# Schematic.net
KiCad netlist of a schematic drawn in Altium Designer
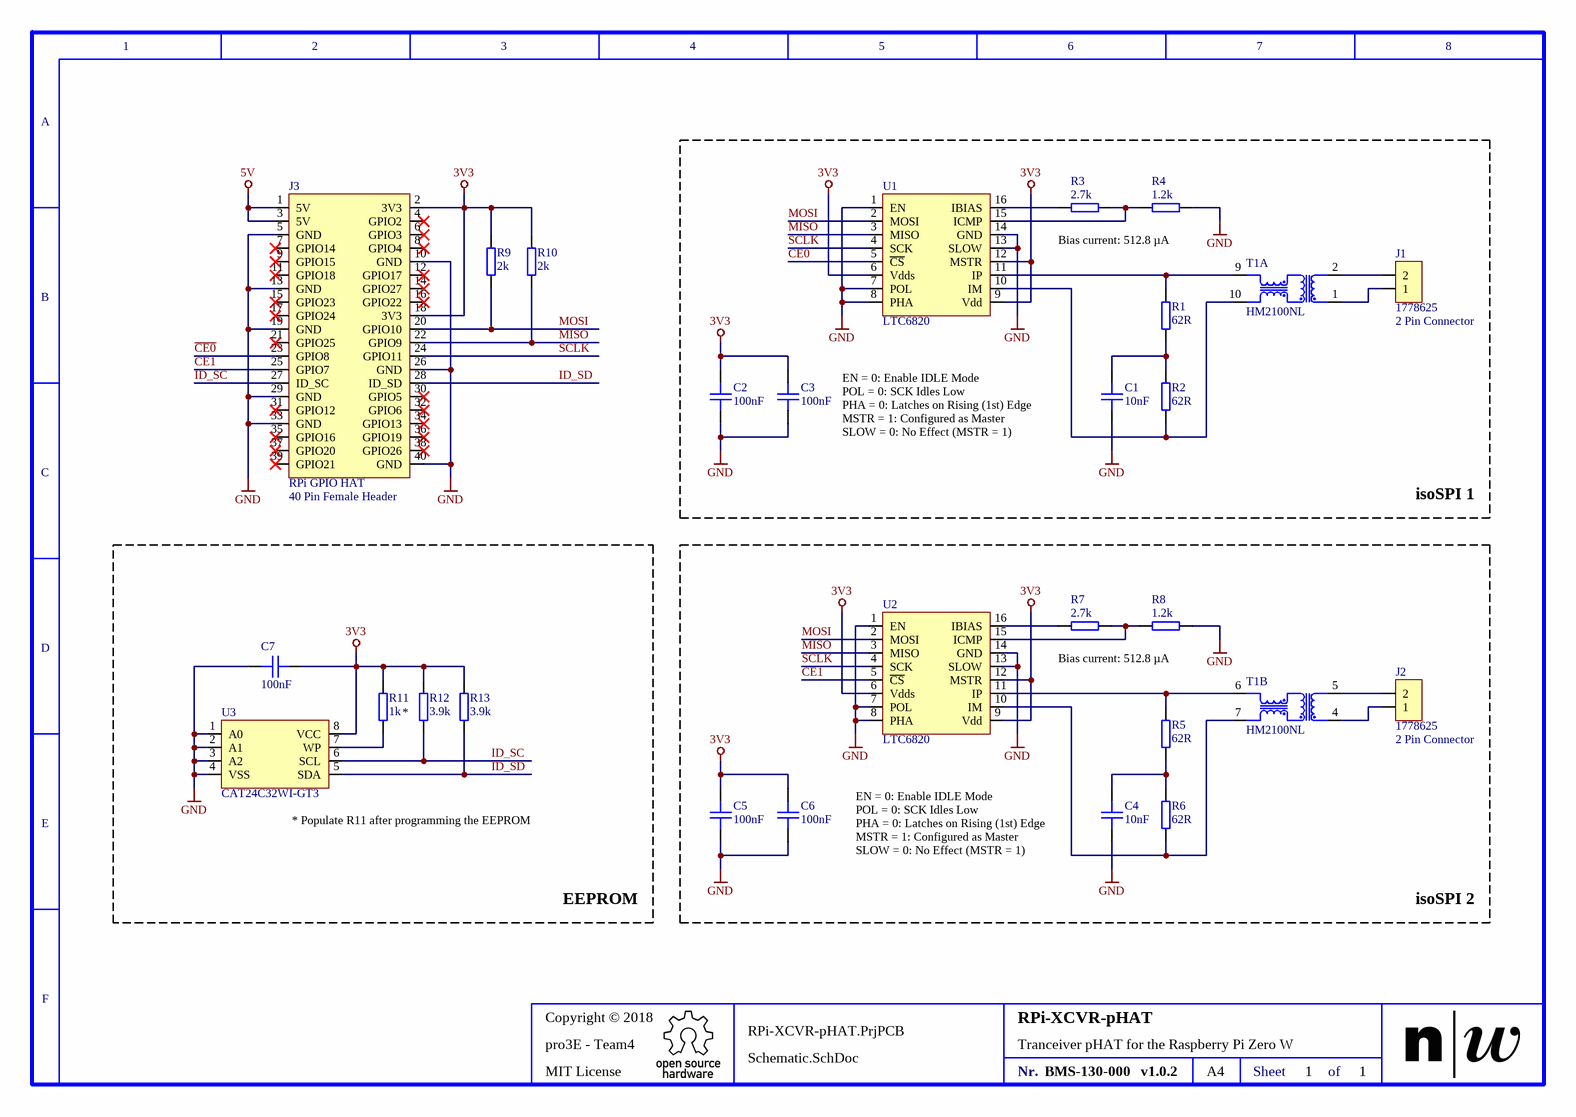
[diagram p0: Schematic.SchDoc]

(export (version "E")
  (design (tool "Eeschema 10.0.6"))
  (components
    (comp (ref "C1") (value "10nF") (footprint "CAP 0603") (libsource (lib "SVNDatabase") (part "Capacitor")))
    (comp (ref "C2")
      (value "100nF")
      (footprint "CAP 0603")
      (libsource (lib "SVNDatabase") (part "Capacitor"))
    )
    (comp (ref "C3")
      (value "100nF")
      (footprint "CAP 0603")
      (libsource (lib "SVNDatabase") (part "Capacitor"))
    )
    (comp (ref "C4") (value "10nF") (footprint "CAP 0603") (libsource (lib "SVNDatabase") (part "Capacitor")))
    (comp (ref "C5")
      (value "100nF")
      (footprint "CAP 0603")
      (libsource (lib "SVNDatabase") (part "Capacitor"))
    )
    (comp (ref "C6")
      (value "100nF")
      (footprint "CAP 0603")
      (libsource (lib "SVNDatabase") (part "Capacitor"))
    )
    (comp (ref "C7")
      (value "100nF")
      (footprint "CAP 0603")
      (libsource (lib "SVNDatabase") (part "Capacitor"))
    )
    (comp (ref "J1")
      (value "1778625")
      (footprint "PTSM 0.5 2 HH THT")
      (description "2 Pin Connector")
      (fields (field (name "DESC") "2 Pin Connector"))
      (libsource (lib "SVNDatabase") (part "2 Pin"))
    )
    (comp (ref "J2")
      (value "1778625")
      (footprint "PTSM 0.5 2 HH THT")
      (description "2 Pin Connector")
      (fields (field (name "DESC") "2 Pin Connector"))
      (libsource (lib "SVNDatabase") (part "2 Pin"))
    )
    (comp (ref "J3")
      (value "RPi GPIO HAT")
      (footprint "Pin Header 2x20 THT 2.54 Female")
      (description "40 Pin Female Header")
      (fields (field (name "DESCR") "40 Pin Female Header"))
      (libsource (lib "SVNDatabase") (part "40 Pin RPi HAT"))
    )
    (comp (ref "R1")
      (value "62R")
      (footprint "0603")
      (fields (field (name "TOLERANCE") "1%"))
      (libsource (lib "SVNDatabase") (part "R"))
    )
    (comp (ref "R2")
      (value "62R")
      (footprint "0603")
      (fields (field (name "TOLERANCE") "1%"))
      (libsource (lib "SVNDatabase") (part "R"))
    )
    (comp (ref "R3")
      (value "2.7k")
      (footprint "0603")
      (fields (field (name "TOLERANCE") "1%"))
      (libsource (lib "SVNDatabase") (part "R"))
    )
    (comp (ref "R4")
      (value "1.2k")
      (footprint "0603")
      (fields (field (name "TOLERANCE") "1%"))
      (libsource (lib "SVNDatabase") (part "R"))
    )
    (comp (ref "R5")
      (value "62R")
      (footprint "0603")
      (fields (field (name "TOLERANCE") "1%"))
      (libsource (lib "SVNDatabase") (part "R"))
    )
    (comp (ref "R6")
      (value "62R")
      (footprint "0603")
      (fields (field (name "TOLERANCE") "1%"))
      (libsource (lib "SVNDatabase") (part "R"))
    )
    (comp (ref "R7")
      (value "2.7k")
      (footprint "0603")
      (fields (field (name "TOLERANCE") "1%"))
      (libsource (lib "SVNDatabase") (part "R"))
    )
    (comp (ref "R8")
      (value "1.2k")
      (footprint "0603")
      (fields (field (name "TOLERANCE") "1%"))
      (libsource (lib "SVNDatabase") (part "R"))
    )
    (comp (ref "R9")
      (value "2k")
      (footprint "0603")
      (fields (field (name "TOLERANCE") "1%"))
      (libsource (lib "SVNDatabase") (part "R"))
    )
    (comp (ref "R10")
      (value "2k")
      (footprint "0603")
      (fields (field (name "TOLERANCE") "1%"))
      (libsource (lib "SVNDatabase") (part "R"))
    )
    (comp (ref "R11")
      (value "1k")
      (footprint "0603")
      (fields (field (name "TOLERANCE") "1%"))
      (libsource (lib "SVNDatabase") (part "R"))
    )
    (comp (ref "R12")
      (value "3.9k")
      (footprint "0603")
      (fields (field (name "TOLERANCE") "1%"))
      (libsource (lib "SVNDatabase") (part "R"))
    )
    (comp (ref "R13")
      (value "3.9k")
      (footprint "0603")
      (fields (field (name "TOLERANCE") "1%"))
      (libsource (lib "SVNDatabase") (part "R"))
    )
    (comp (ref "T1")
      (value "HM2100NL")
      (footprint "HM2100NL")
      (description "BMS Communication Transformer with Choke")
      (fields (field (name "TOLERANCE") "50%"))
      (libsource (lib "") (part "HM2100NL_1"))
    )
    (comp (ref "U1")
      (value "LTC6820")
      (footprint "MSOP-16")
      (description "Isolated SPI Communications Interface")
      (libsource (lib "SVNDatabase") (part "LTC6820"))
    )
    (comp (ref "U2")
      (value "LTC6820")
      (footprint "MSOP-16")
      (description "Isolated SPI Communications Interface")
      (libsource (lib "SVNDatabase") (part "LTC6820"))
    )
    (comp (ref "U3")
      (value "CAT24C32WI-GT3")
      (footprint "SO-8")
      (description "EEPROM Memory IC 32Kb")
      (libsource (lib "SVNDatabase") (part "CAT24C32"))
    )
  )
  (nets
    (net (code "1") (name "/ID_SC") (class "Default")
      (node (ref "J3") (pin "27") (pinfunction "ID_SC_27") (pintype "passive"))
      (node (ref "R12") (pin "1") (pinfunction "1_1") (pintype "passive"))
      (node (ref "U3") (pin "6") (pinfunction "SCL_6") (pintype "passive"))
    )
    (net (code "2") (name "/ID_SD") (class "Default")
      (node (ref "J3") (pin "28") (pinfunction "ID_SD_28") (pintype "passive"))
      (node (ref "R13") (pin "1") (pinfunction "1_1") (pintype "passive"))
      (node (ref "U3") (pin "5") (pinfunction "SDA_5") (pintype "passive"))
    )
    (net (code "3") (name "/MISO") (class "Default")
      (node (ref "J3") (pin "22") (pinfunction "GPIO9_22") (pintype "passive"))
      (node (ref "R10") (pin "1") (pinfunction "1_1") (pintype "passive"))
      (node (ref "U1") (pin "3") (pinfunction "MISO_3") (pintype "passive"))
      (node (ref "U2") (pin "3") (pinfunction "MISO_3") (pintype "passive"))
    )
    (net (code "4") (name "/MOSI") (class "Default")
      (node (ref "J3") (pin "20") (pinfunction "GPIO10_20") (pintype "passive"))
      (node (ref "R9") (pin "1") (pinfunction "1_1") (pintype "passive"))
      (node (ref "U1") (pin "2") (pinfunction "MOSI_2") (pintype "passive"))
      (node (ref "U2") (pin "2") (pinfunction "MOSI_2") (pintype "passive"))
    )
    (net (code "5") (name "/SCLK") (class "Default")
      (node (ref "J3") (pin "24") (pinfunction "GPIO11_24") (pintype "passive"))
      (node (ref "U1") (pin "4") (pinfunction "SCK_4") (pintype "passive"))
      (node (ref "U2") (pin "4") (pinfunction "SCK_4") (pintype "passive"))
    )
    (net (code "6") (name "/~{CE0}") (class "Default")
      (node (ref "J3") (pin "23") (pinfunction "GPIO8_23") (pintype "passive"))
      (node (ref "U1") (pin "5") (pinfunction "~{CS}_5") (pintype "passive"))
    )
    (net (code "7") (name "/~{CE1}") (class "Default")
      (node (ref "J3") (pin "25") (pinfunction "GPIO7_25") (pintype "passive"))
      (node (ref "U2") (pin "5") (pinfunction "~{CS}_5") (pintype "passive"))
    )
    (net (code "8") (name "3V3") (class "Default")
      (node (ref "C2") (pin "2") (pinfunction "2_2") (pintype "passive"))
      (node (ref "C3") (pin "2") (pinfunction "2_2") (pintype "passive"))
      (node (ref "C5") (pin "2") (pinfunction "2_2") (pintype "passive"))
      (node (ref "C6") (pin "2") (pinfunction "2_2") (pintype "passive"))
      (node (ref "C7") (pin "1") (pinfunction "1_1") (pintype "passive"))
      (node (ref "J3") (pin "18") (pinfunction "3V3_18") (pintype "passive"))
      (node (ref "J3") (pin "2") (pinfunction "3V3_2") (pintype "passive"))
      (node (ref "R10") (pin "2") (pinfunction "2_2") (pintype "passive"))
      (node (ref "R11") (pin "2") (pinfunction "2_2") (pintype "passive"))
      (node (ref "R12") (pin "2") (pinfunction "2_2") (pintype "passive"))
      (node (ref "R13") (pin "2") (pinfunction "2_2") (pintype "passive"))
      (node (ref "R9") (pin "2") (pinfunction "2_2") (pintype "passive"))
      (node (ref "U1") (pin "12") (pinfunction "MSTR_12") (pintype "passive"))
      (node (ref "U1") (pin "6") (pinfunction "Vdds_6") (pintype "passive"))
      (node (ref "U1") (pin "9") (pinfunction "Vdd_9") (pintype "passive"))
      (node (ref "U2") (pin "12") (pinfunction "MSTR_12") (pintype "passive"))
      (node (ref "U2") (pin "6") (pinfunction "Vdds_6") (pintype "passive"))
      (node (ref "U2") (pin "9") (pinfunction "Vdd_9") (pintype "passive"))
      (node (ref "U3") (pin "8") (pinfunction "VCC_8") (pintype "passive"))
    )
    (net (code "9") (name "5V") (class "Default")
      (node (ref "J3") (pin "1") (pinfunction "5V_1") (pintype "passive"))
      (node (ref "J3") (pin "3") (pinfunction "5V_3") (pintype "passive"))
    )
    (net (code "10") (name "GND") (class "Default")
      (node (ref "C1") (pin "1") (pinfunction "1_1") (pintype "passive"))
      (node (ref "C2") (pin "1") (pinfunction "1_1") (pintype "passive"))
      (node (ref "C3") (pin "1") (pinfunction "1_1") (pintype "passive"))
      (node (ref "C4") (pin "1") (pinfunction "1_1") (pintype "passive"))
      (node (ref "C5") (pin "1") (pinfunction "1_1") (pintype "passive"))
      (node (ref "C6") (pin "1") (pinfunction "1_1") (pintype "passive"))
      (node (ref "C7") (pin "2") (pinfunction "2_2") (pintype "passive"))
      (node (ref "J3") (pin "10") (pinfunction "GND_10") (pintype "passive"))
      (node (ref "J3") (pin "13") (pinfunction "GND_13") (pintype "passive"))
      (node (ref "J3") (pin "19") (pinfunction "GND_19") (pintype "passive"))
      (node (ref "J3") (pin "26") (pinfunction "GND_26") (pintype "passive"))
      (node (ref "J3") (pin "29") (pinfunction "GND_29") (pintype "passive"))
      (node (ref "J3") (pin "33") (pinfunction "GND_33") (pintype "passive"))
      (node (ref "J3") (pin "40") (pinfunction "GND_40") (pintype "passive"))
      (node (ref "J3") (pin "5") (pinfunction "GND_5") (pintype "passive"))
      (node (ref "R4") (pin "2") (pinfunction "2_2") (pintype "passive"))
      (node (ref "R8") (pin "2") (pinfunction "2_2") (pintype "passive"))
      (node (ref "U1") (pin "1") (pinfunction "EN_1") (pintype "passive"))
      (node (ref "U1") (pin "13") (pinfunction "SLOW_13") (pintype "passive"))
      (node (ref "U1") (pin "14") (pinfunction "GND_14") (pintype "passive"))
      (node (ref "U1") (pin "7") (pinfunction "POL_7") (pintype "passive"))
      (node (ref "U1") (pin "8") (pinfunction "PHA_8") (pintype "passive"))
      (node (ref "U2") (pin "1") (pinfunction "EN_1") (pintype "passive"))
      (node (ref "U2") (pin "13") (pinfunction "SLOW_13") (pintype "passive"))
      (node (ref "U2") (pin "14") (pinfunction "GND_14") (pintype "passive"))
      (node (ref "U2") (pin "7") (pinfunction "POL_7") (pintype "passive"))
      (node (ref "U2") (pin "8") (pinfunction "PHA_8") (pintype "passive"))
      (node (ref "U3") (pin "1") (pinfunction "A0_1") (pintype "passive"))
      (node (ref "U3") (pin "2") (pinfunction "A1_2") (pintype "passive"))
      (node (ref "U3") (pin "3") (pinfunction "A2_3") (pintype "passive"))
      (node (ref "U3") (pin "4") (pinfunction "VSS_4") (pintype "passive"))
    )
    (net (code "11") (name "Net-(C1-Pad2)") (class "Default")
      (node (ref "C1") (pin "2") (pinfunction "2_2") (pintype "passive"))
      (node (ref "R1") (pin "1") (pinfunction "1_1") (pintype "passive"))
      (node (ref "R2") (pin "2") (pinfunction "2_2") (pintype "passive"))
    )
    (net (code "12") (name "Net-(C4-Pad2)") (class "Default")
      (node (ref "C4") (pin "2") (pinfunction "2_2") (pintype "passive"))
      (node (ref "R5") (pin "1") (pinfunction "1_1") (pintype "passive"))
      (node (ref "R6") (pin "2") (pinfunction "2_2") (pintype "passive"))
    )
    (net (code "13") (name "Net-(J1-Pad1)") (class "Default")
      (node (ref "J1") (pin "1") (pinfunction "1_1") (pintype "passive"))
      (node (ref "T1") (pin "1") (pinfunction "1_1") (pintype "passive"))
    )
    (net (code "14") (name "Net-(J1-Pad2)") (class "Default")
      (node (ref "J1") (pin "2") (pinfunction "2_2") (pintype "passive"))
      (node (ref "T1") (pin "2") (pinfunction "2_2") (pintype "passive"))
    )
    (net (code "15") (name "Net-(J2-Pad1)") (class "Default")
      (node (ref "J2") (pin "1") (pinfunction "1_1") (pintype "passive"))
      (node (ref "T1") (pin "4") (pinfunction "4_4") (pintype "passive"))
    )
    (net (code "16") (name "Net-(J2-Pad2)") (class "Default")
      (node (ref "J2") (pin "2") (pinfunction "2_2") (pintype "passive"))
      (node (ref "T1") (pin "5") (pinfunction "5_5") (pintype "passive"))
    )
    (net (code "17") (name "Net-(U1-IBIAS)") (class "Default")
      (node (ref "R3") (pin "1") (pinfunction "1_1") (pintype "passive"))
      (node (ref "U1") (pin "16") (pinfunction "IBIAS_16") (pintype "passive"))
    )
    (net (code "18") (name "Net-(U1-ICMP)") (class "Default")
      (node (ref "R3") (pin "2") (pinfunction "2_2") (pintype "passive"))
      (node (ref "R4") (pin "1") (pinfunction "1_1") (pintype "passive"))
      (node (ref "U1") (pin "15") (pinfunction "ICMP_15") (pintype "passive"))
    )
    (net (code "19") (name "Net-(U1-IM)") (class "Default")
      (node (ref "R2") (pin "1") (pinfunction "1_1") (pintype "passive"))
      (node (ref "T1") (pin "10") (pinfunction "10_10") (pintype "passive"))
      (node (ref "U1") (pin "10") (pinfunction "IM_10") (pintype "passive"))
    )
    (net (code "20") (name "Net-(U1-IP)") (class "Default")
      (node (ref "R1") (pin "2") (pinfunction "2_2") (pintype "passive"))
      (node (ref "T1") (pin "9") (pinfunction "9_9") (pintype "passive"))
      (node (ref "U1") (pin "11") (pinfunction "IP_11") (pintype "passive"))
    )
    (net (code "21") (name "Net-(U2-IBIAS)") (class "Default")
      (node (ref "R7") (pin "1") (pinfunction "1_1") (pintype "passive"))
      (node (ref "U2") (pin "16") (pinfunction "IBIAS_16") (pintype "passive"))
    )
    (net (code "22") (name "Net-(U2-ICMP)") (class "Default")
      (node (ref "R7") (pin "2") (pinfunction "2_2") (pintype "passive"))
      (node (ref "R8") (pin "1") (pinfunction "1_1") (pintype "passive"))
      (node (ref "U2") (pin "15") (pinfunction "ICMP_15") (pintype "passive"))
    )
    (net (code "23") (name "Net-(U2-IM)") (class "Default")
      (node (ref "R6") (pin "1") (pinfunction "1_1") (pintype "passive"))
      (node (ref "T1") (pin "7") (pinfunction "7_7") (pintype "passive"))
      (node (ref "U2") (pin "10") (pinfunction "IM_10") (pintype "passive"))
    )
    (net (code "24") (name "Net-(U2-IP)") (class "Default")
      (node (ref "R5") (pin "2") (pinfunction "2_2") (pintype "passive"))
      (node (ref "T1") (pin "6") (pinfunction "6_6") (pintype "passive"))
      (node (ref "U2") (pin "11") (pinfunction "IP_11") (pintype "passive"))
    )
    (net (code "25") (name "Net-(U3-WP)") (class "Default")
      (node (ref "R11") (pin "1") (pinfunction "1_1") (pintype "passive"))
      (node (ref "U3") (pin "7") (pinfunction "WP_7") (pintype "passive"))
    )
    (net (code "26") (name "unconnected-(J3-GPIO2-Pad4)") (class "Default")
      (node (ref "J3") (pin "4") (pinfunction "GPIO2_4") (pintype "passive+no_connect"))
    )
    (net (code "27") (name "unconnected-(J3-GPIO3-Pad6)") (class "Default")
      (node (ref "J3") (pin "6") (pinfunction "GPIO3_6") (pintype "passive+no_connect"))
    )
    (net (code "28") (name "unconnected-(J3-GPIO4-Pad8)") (class "Default")
      (node (ref "J3") (pin "8") (pinfunction "GPIO4_8") (pintype "passive+no_connect"))
    )
    (net (code "29") (name "unconnected-(J3-GPIO5-Pad30)") (class "Default")
      (node (ref "J3") (pin "30") (pinfunction "GPIO5_30") (pintype "passive+no_connect"))
    )
    (net (code "30") (name "unconnected-(J3-GPIO6-Pad32)") (class "Default")
      (node (ref "J3") (pin "32") (pinfunction "GPIO6_32") (pintype "passive+no_connect"))
    )
    (net (code "31") (name "unconnected-(J3-GPIO12-Pad31)") (class "Default")
      (node (ref "J3") (pin "31") (pinfunction "GPIO12_31") (pintype "passive+no_connect"))
    )
    (net (code "32") (name "unconnected-(J3-GPIO13-Pad34)") (class "Default")
      (node (ref "J3") (pin "34") (pinfunction "GPIO13_34") (pintype "passive+no_connect"))
    )
    (net (code "33") (name "unconnected-(J3-GPIO14-Pad7)") (class "Default")
      (node (ref "J3") (pin "7") (pinfunction "GPIO14_7") (pintype "passive+no_connect"))
    )
    (net (code "34") (name "unconnected-(J3-GPIO15-Pad9)") (class "Default")
      (node (ref "J3") (pin "9") (pinfunction "GPIO15_9") (pintype "passive+no_connect"))
    )
    (net (code "35") (name "unconnected-(J3-GPIO16-Pad35)") (class "Default")
      (node (ref "J3") (pin "35") (pinfunction "GPIO16_35") (pintype "passive+no_connect"))
    )
    (net (code "36") (name "unconnected-(J3-GPIO17-Pad12)") (class "Default")
      (node (ref "J3") (pin "12") (pinfunction "GPIO17_12") (pintype "passive+no_connect"))
    )
    (net (code "37") (name "unconnected-(J3-GPIO18-Pad11)") (class "Default")
      (node (ref "J3") (pin "11") (pinfunction "GPIO18_11") (pintype "passive+no_connect"))
    )
    (net (code "38") (name "unconnected-(J3-GPIO19-Pad36)") (class "Default")
      (node (ref "J3") (pin "36") (pinfunction "GPIO19_36") (pintype "passive+no_connect"))
    )
    (net (code "39") (name "unconnected-(J3-GPIO20-Pad37)") (class "Default")
      (node (ref "J3") (pin "37") (pinfunction "GPIO20_37") (pintype "passive+no_connect"))
    )
    (net (code "40") (name "unconnected-(J3-GPIO21-Pad39)") (class "Default")
      (node (ref "J3") (pin "39") (pinfunction "GPIO21_39") (pintype "passive+no_connect"))
    )
    (net (code "41") (name "unconnected-(J3-GPIO22-Pad16)") (class "Default")
      (node (ref "J3") (pin "16") (pinfunction "GPIO22_16") (pintype "passive+no_connect"))
    )
    (net (code "42") (name "unconnected-(J3-GPIO23-Pad15)") (class "Default")
      (node (ref "J3") (pin "15") (pinfunction "GPIO23_15") (pintype "passive+no_connect"))
    )
    (net (code "43") (name "unconnected-(J3-GPIO24-Pad17)") (class "Default")
      (node (ref "J3") (pin "17") (pinfunction "GPIO24_17") (pintype "passive+no_connect"))
    )
    (net (code "44") (name "unconnected-(J3-GPIO25-Pad21)") (class "Default")
      (node (ref "J3") (pin "21") (pinfunction "GPIO25_21") (pintype "passive+no_connect"))
    )
    (net (code "45") (name "unconnected-(J3-GPIO26-Pad38)") (class "Default")
      (node (ref "J3") (pin "38") (pinfunction "GPIO26_38") (pintype "passive+no_connect"))
    )
    (net (code "46") (name "unconnected-(J3-GPIO27-Pad14)") (class "Default")
      (node (ref "J3") (pin "14") (pinfunction "GPIO27_14") (pintype "passive+no_connect"))
    )
  )
)
